# nine_poke_i2c.net
KiCad netlist of a schematic drawn in EAGLE
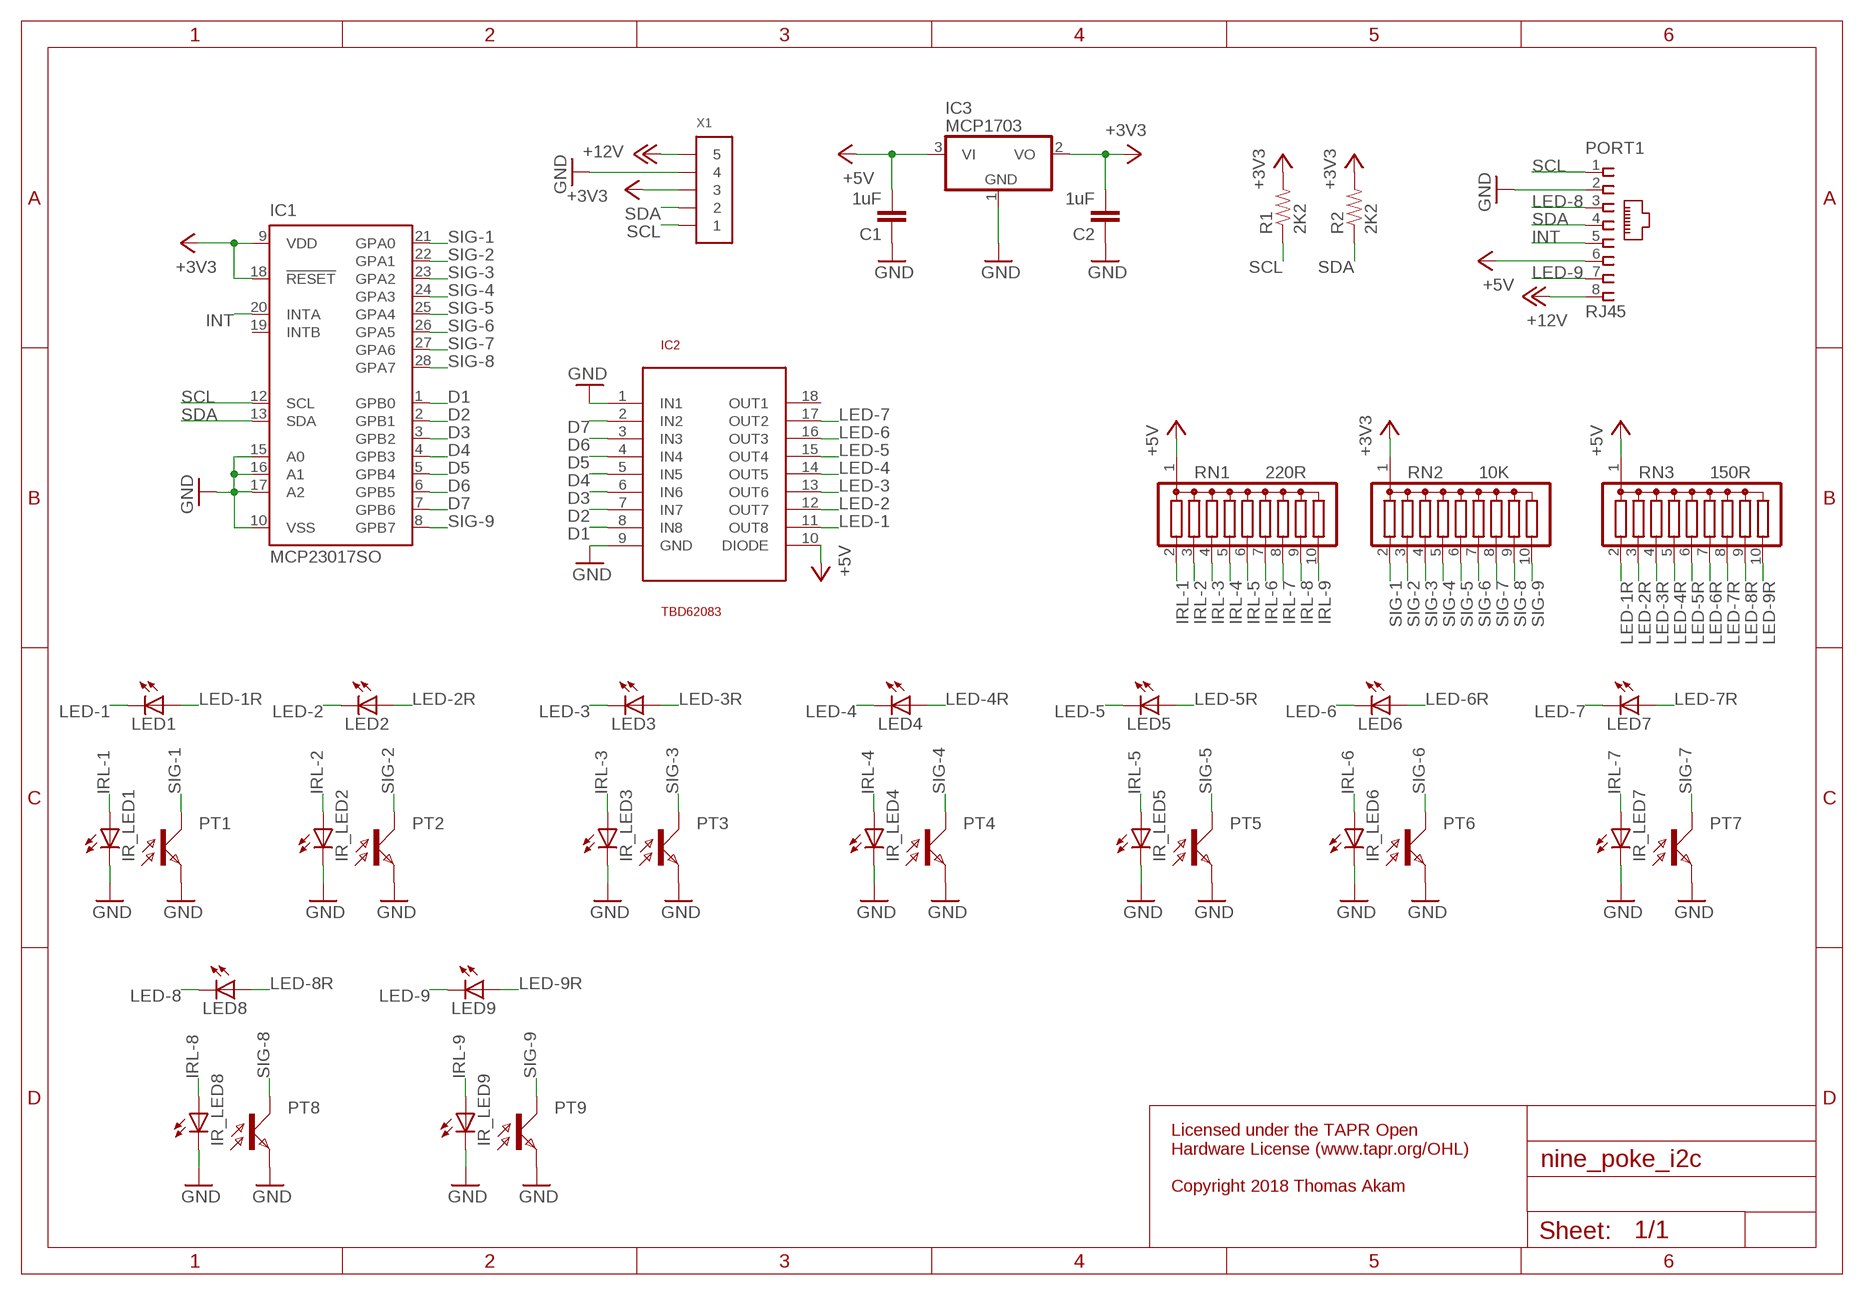
[diagram p0: schematic, sheet 1]

(export (version "E")
  (design (tool "Eeschema 10.0.6"))
  (components
    (comp (ref "C1")
      (value "1uF")
      (footprint "eagle-import:C0805")
      (libsource (lib "eagle-import") (part "C-EUC0805"))
    )
    (comp (ref "C2")
      (value "1uF")
      (footprint "eagle-import:C0805")
      (libsource (lib "eagle-import") (part "C-EUC0805"))
    )
    (comp (ref "IC1")
      (value "MCP23017SO")
      (footprint "eagle-import:SO28W")
      (fields (field (name "MF") "MICROCHIP") (field (name "MPN") "MCP23017-E/SO"))
      (libsource (lib "eagle-import") (part "MCP23017SO"))
    )
    (comp (ref "IC2")
      (value "TBD62083")
      (footprint "eagle-import:SO18L")
      (libsource (lib "eagle-import") (part "ULN2803"))
    )
    (comp (ref "IC3")
      (value "MCP1703")
      (footprint "eagle-import:SOT23")
      (libsource (lib "eagle-import") (part "MCP1703CB"))
    )
    (comp (ref "IR_LED1")
      (value "LEDIRL80A")
      (footprint "eagle-import:IRL80A")
      (libsource (lib "eagle-import") (part "LEDIRL80A"))
    )
    (comp (ref "IR_LED2")
      (value "LEDIRL80A")
      (footprint "eagle-import:IRL80A")
      (libsource (lib "eagle-import") (part "LEDIRL80A"))
    )
    (comp (ref "IR_LED3")
      (value "LEDIRL80A")
      (footprint "eagle-import:IRL80A")
      (libsource (lib "eagle-import") (part "LEDIRL80A"))
    )
    (comp (ref "IR_LED4")
      (value "LEDIRL80A")
      (footprint "eagle-import:IRL80A")
      (libsource (lib "eagle-import") (part "LEDIRL80A"))
    )
    (comp (ref "IR_LED5")
      (value "LEDIRL80A")
      (footprint "eagle-import:IRL80A")
      (libsource (lib "eagle-import") (part "LEDIRL80A"))
    )
    (comp (ref "IR_LED6")
      (value "LEDIRL80A")
      (footprint "eagle-import:IRL80A")
      (libsource (lib "eagle-import") (part "LEDIRL80A"))
    )
    (comp (ref "IR_LED7")
      (value "LEDIRL80A")
      (footprint "eagle-import:IRL80A")
      (libsource (lib "eagle-import") (part "LEDIRL80A"))
    )
    (comp (ref "IR_LED8")
      (value "LEDIRL80A")
      (footprint "eagle-import:IRL80A")
      (libsource (lib "eagle-import") (part "LEDIRL80A"))
    )
    (comp (ref "IR_LED9")
      (value "LEDIRL80A")
      (footprint "eagle-import:IRL80A")
      (libsource (lib "eagle-import") (part "LEDIRL80A"))
    )
    (comp (ref "LED1")
      (value "LEDSML0805")
      (footprint "eagle-import:SML0805")
      (libsource (lib "eagle-import") (part "LEDSML0805"))
    )
    (comp (ref "LED2")
      (value "LEDSML0805")
      (footprint "eagle-import:SML0805")
      (libsource (lib "eagle-import") (part "LEDSML0805"))
    )
    (comp (ref "LED3")
      (value "LEDSML0805")
      (footprint "eagle-import:SML0805")
      (libsource (lib "eagle-import") (part "LEDSML0805"))
    )
    (comp (ref "LED4")
      (value "LEDSML0805")
      (footprint "eagle-import:SML0805")
      (libsource (lib "eagle-import") (part "LEDSML0805"))
    )
    (comp (ref "LED5")
      (value "LEDSML0805")
      (footprint "eagle-import:SML0805")
      (libsource (lib "eagle-import") (part "LEDSML0805"))
    )
    (comp (ref "LED6")
      (value "LEDSML0805")
      (footprint "eagle-import:SML0805")
      (libsource (lib "eagle-import") (part "LEDSML0805"))
    )
    (comp (ref "LED7")
      (value "LEDSML0805")
      (footprint "eagle-import:SML0805")
      (libsource (lib "eagle-import") (part "LEDSML0805"))
    )
    (comp (ref "LED8")
      (value "LEDSML0805")
      (footprint "eagle-import:SML0805")
      (libsource (lib "eagle-import") (part "LEDSML0805"))
    )
    (comp (ref "LED9")
      (value "LEDSML0805")
      (footprint "eagle-import:SML0805")
      (libsource (lib "eagle-import") (part "LEDSML0805"))
    )
    (comp (ref "PORT1")
      (value "RJ45")
      (footprint "eagle-import:RJ45-NO-SHIELD-VERTICAL")
      (libsource (lib "eagle-import") (part "RJ45VERTICAL"))
    )
    (comp (ref "PT1")
      (value "LPT80A")
      (footprint "eagle-import:LPT80A")
      (fields (field (name "OC_FARNELL") "unknown") (field (name "OC_NEWARK") "unknown"))
      (libsource (lib "eagle-import") (part "LPT80A"))
    )
    (comp (ref "PT2")
      (value "LPT80A")
      (footprint "eagle-import:LPT80A")
      (fields (field (name "OC_FARNELL") "unknown") (field (name "OC_NEWARK") "unknown"))
      (libsource (lib "eagle-import") (part "LPT80A"))
    )
    (comp (ref "PT3")
      (value "LPT80A")
      (footprint "eagle-import:LPT80A")
      (fields (field (name "OC_FARNELL") "unknown") (field (name "OC_NEWARK") "unknown"))
      (libsource (lib "eagle-import") (part "LPT80A"))
    )
    (comp (ref "PT4")
      (value "LPT80A")
      (footprint "eagle-import:LPT80A")
      (fields (field (name "OC_FARNELL") "unknown") (field (name "OC_NEWARK") "unknown"))
      (libsource (lib "eagle-import") (part "LPT80A"))
    )
    (comp (ref "PT5")
      (value "LPT80A")
      (footprint "eagle-import:LPT80A")
      (fields (field (name "OC_FARNELL") "unknown") (field (name "OC_NEWARK") "unknown"))
      (libsource (lib "eagle-import") (part "LPT80A"))
    )
    (comp (ref "PT6")
      (value "LPT80A")
      (footprint "eagle-import:LPT80A")
      (fields (field (name "OC_FARNELL") "unknown") (field (name "OC_NEWARK") "unknown"))
      (libsource (lib "eagle-import") (part "LPT80A"))
    )
    (comp (ref "PT7")
      (value "LPT80A")
      (footprint "eagle-import:LPT80A")
      (fields (field (name "OC_FARNELL") "unknown") (field (name "OC_NEWARK") "unknown"))
      (libsource (lib "eagle-import") (part "LPT80A"))
    )
    (comp (ref "PT8")
      (value "LPT80A")
      (footprint "eagle-import:LPT80A")
      (fields (field (name "OC_FARNELL") "unknown") (field (name "OC_NEWARK") "unknown"))
      (libsource (lib "eagle-import") (part "LPT80A"))
    )
    (comp (ref "PT9")
      (value "LPT80A")
      (footprint "eagle-import:LPT80A")
      (fields (field (name "OC_FARNELL") "unknown") (field (name "OC_NEWARK") "unknown"))
      (libsource (lib "eagle-import") (part "LPT80A"))
    )
    (comp (ref "R1")
      (value "2K2")
      (footprint "eagle-import:0805")
      (libsource (lib "eagle-import") (part "0.3OHM-1/8W-1%(0805)"))
    )
    (comp (ref "R2")
      (value "2K2")
      (footprint "eagle-import:0805")
      (libsource (lib "eagle-import") (part "0.3OHM-1/8W-1%(0805)"))
    )
    (comp (ref "RN1")
      (value "220R")
      (footprint "eagle-import:SIL10")
      (libsource (lib "eagle-import") (part "G09R"))
    )
    (comp (ref "RN2")
      (value "10K")
      (footprint "eagle-import:SIL10")
      (libsource (lib "eagle-import") (part "G09R"))
    )
    (comp (ref "RN3")
      (value "150R")
      (footprint "eagle-import:SIL10")
      (libsource (lib "eagle-import") (part "G09R"))
    )
    (comp (ref "X1")
      (value "CONN_5-1-53398")
      (footprint "eagle-import:PB-53398-05")
      (libsource (lib "eagle-import") (part "CONN_5-1-53398"))
    )
  )
  (nets
    (net (code "1") (name "+3V3") (class "Default")
      (node (ref "C2") (pin "2") (pinfunction "2_2") (pintype "passive"))
      (node (ref "IC1") (pin "18") (pinfunction "~{RESET}_18") (pintype "input"))
      (node (ref "IC1") (pin "9") (pinfunction "VDD_9") (pintype "power_in"))
      (node (ref "IC3") (pin "2") (pinfunction "VO_2") (pintype "passive"))
      (node (ref "R1") (pin "2") (pinfunction "2_2") (pintype "passive"))
      (node (ref "R2") (pin "2") (pinfunction "2_2") (pintype "passive"))
      (node (ref "RN2") (pin "1") (pinfunction "1_1") (pintype "passive"))
      (node (ref "X1") (pin "3") (pinfunction "3_3") (pintype "bidirectional"))
    )
    (net (code "2") (name "+5V") (class "Default")
      (node (ref "C1") (pin "2") (pinfunction "2_2") (pintype "passive"))
      (node (ref "IC2") (pin "10") (pinfunction "DIODE_10") (pintype "power_in"))
      (node (ref "IC3") (pin "3") (pinfunction "VI_3") (pintype "input"))
      (node (ref "PORT1") (pin "6") (pinfunction "6_6") (pintype "passive"))
      (node (ref "RN1") (pin "1") (pinfunction "1_1") (pintype "passive"))
      (node (ref "RN3") (pin "1") (pinfunction "1_1") (pintype "passive"))
    )
    (net (code "3") (name "+12V") (class "Default")
      (node (ref "PORT1") (pin "8") (pinfunction "8_8") (pintype "passive"))
      (node (ref "X1") (pin "5") (pinfunction "5_5") (pintype "bidirectional"))
    )
    (net (code "4") (name "/D1") (class "Default")
      (node (ref "IC1") (pin "1") (pinfunction "GPB0_1") (pintype "bidirectional"))
      (node (ref "IC2") (pin "8") (pinfunction "IN8_8") (pintype "input"))
    )
    (net (code "5") (name "/D2") (class "Default")
      (node (ref "IC1") (pin "2") (pinfunction "GPB1_2") (pintype "bidirectional"))
      (node (ref "IC2") (pin "7") (pinfunction "IN7_7") (pintype "input"))
    )
    (net (code "6") (name "/D3") (class "Default")
      (node (ref "IC1") (pin "3") (pinfunction "GPB2_3") (pintype "bidirectional"))
      (node (ref "IC2") (pin "6") (pinfunction "IN6_6") (pintype "input"))
    )
    (net (code "7") (name "/D4") (class "Default")
      (node (ref "IC1") (pin "4") (pinfunction "GPB3_4") (pintype "bidirectional"))
      (node (ref "IC2") (pin "5") (pinfunction "IN5_5") (pintype "input"))
    )
    (net (code "8") (name "/D5") (class "Default")
      (node (ref "IC1") (pin "5") (pinfunction "GPB4_5") (pintype "bidirectional"))
      (node (ref "IC2") (pin "4") (pinfunction "IN4_4") (pintype "input"))
    )
    (net (code "9") (name "/D6") (class "Default")
      (node (ref "IC1") (pin "6") (pinfunction "GPB5_6") (pintype "bidirectional"))
      (node (ref "IC2") (pin "3") (pinfunction "IN3_3") (pintype "input"))
    )
    (net (code "10") (name "/D7") (class "Default")
      (node (ref "IC1") (pin "7") (pinfunction "GPB6_7") (pintype "bidirectional"))
      (node (ref "IC2") (pin "2") (pinfunction "IN2_2") (pintype "input"))
    )
    (net (code "11") (name "/INT") (class "Default")
      (node (ref "IC1") (pin "20") (pinfunction "INTA_20") (pintype "output"))
      (node (ref "PORT1") (pin "5") (pinfunction "5_5") (pintype "passive"))
    )
    (net (code "12") (name "/IRL-1") (class "Default")
      (node (ref "IR_LED1") (pin "A") (pinfunction "A_A") (pintype "passive"))
      (node (ref "RN1") (pin "2") (pinfunction "2_2") (pintype "passive"))
    )
    (net (code "13") (name "/IRL-2") (class "Default")
      (node (ref "IR_LED2") (pin "A") (pinfunction "A_A") (pintype "passive"))
      (node (ref "RN1") (pin "3") (pinfunction "3_3") (pintype "passive"))
    )
    (net (code "14") (name "/IRL-3") (class "Default")
      (node (ref "IR_LED3") (pin "A") (pinfunction "A_A") (pintype "passive"))
      (node (ref "RN1") (pin "4") (pinfunction "4_4") (pintype "passive"))
    )
    (net (code "15") (name "/IRL-4") (class "Default")
      (node (ref "IR_LED4") (pin "A") (pinfunction "A_A") (pintype "passive"))
      (node (ref "RN1") (pin "5") (pinfunction "5_5") (pintype "passive"))
    )
    (net (code "16") (name "/IRL-5") (class "Default")
      (node (ref "IR_LED5") (pin "A") (pinfunction "A_A") (pintype "passive"))
      (node (ref "RN1") (pin "6") (pinfunction "6_6") (pintype "passive"))
    )
    (net (code "17") (name "/IRL-6") (class "Default")
      (node (ref "IR_LED6") (pin "A") (pinfunction "A_A") (pintype "passive"))
      (node (ref "RN1") (pin "7") (pinfunction "7_7") (pintype "passive"))
    )
    (net (code "18") (name "/IRL-7") (class "Default")
      (node (ref "IR_LED7") (pin "A") (pinfunction "A_A") (pintype "passive"))
      (node (ref "RN1") (pin "8") (pinfunction "8_8") (pintype "passive"))
    )
    (net (code "19") (name "/IRL-8") (class "Default")
      (node (ref "IR_LED8") (pin "A") (pinfunction "A_A") (pintype "passive"))
      (node (ref "RN1") (pin "9") (pinfunction "9_9") (pintype "passive"))
    )
    (net (code "20") (name "/IRL-9") (class "Default")
      (node (ref "IR_LED9") (pin "A") (pinfunction "A_A") (pintype "passive"))
      (node (ref "RN1") (pin "10") (pinfunction "10_10") (pintype "passive"))
    )
    (net (code "21") (name "/LED-1") (class "Default")
      (node (ref "IC2") (pin "11") (pinfunction "OUT8_11") (pintype "open_collector"))
      (node (ref "LED1") (pin "C") (pinfunction "C_C") (pintype "passive"))
    )
    (net (code "22") (name "/LED-1R") (class "Default")
      (node (ref "LED1") (pin "A") (pinfunction "A_A") (pintype "passive"))
      (node (ref "RN3") (pin "2") (pinfunction "2_2") (pintype "passive"))
    )
    (net (code "23") (name "/LED-2") (class "Default")
      (node (ref "IC2") (pin "12") (pinfunction "OUT7_12") (pintype "open_collector"))
      (node (ref "LED2") (pin "C") (pinfunction "C_C") (pintype "passive"))
    )
    (net (code "24") (name "/LED-2R") (class "Default")
      (node (ref "LED2") (pin "A") (pinfunction "A_A") (pintype "passive"))
      (node (ref "RN3") (pin "3") (pinfunction "3_3") (pintype "passive"))
    )
    (net (code "25") (name "/LED-3") (class "Default")
      (node (ref "IC2") (pin "13") (pinfunction "OUT6_13") (pintype "open_collector"))
      (node (ref "LED3") (pin "C") (pinfunction "C_C") (pintype "passive"))
    )
    (net (code "26") (name "/LED-3R") (class "Default")
      (node (ref "LED3") (pin "A") (pinfunction "A_A") (pintype "passive"))
      (node (ref "RN3") (pin "4") (pinfunction "4_4") (pintype "passive"))
    )
    (net (code "27") (name "/LED-4") (class "Default")
      (node (ref "IC2") (pin "14") (pinfunction "OUT5_14") (pintype "open_collector"))
      (node (ref "LED4") (pin "C") (pinfunction "C_C") (pintype "passive"))
    )
    (net (code "28") (name "/LED-4R") (class "Default")
      (node (ref "LED4") (pin "A") (pinfunction "A_A") (pintype "passive"))
      (node (ref "RN3") (pin "5") (pinfunction "5_5") (pintype "passive"))
    )
    (net (code "29") (name "/LED-5") (class "Default")
      (node (ref "IC2") (pin "15") (pinfunction "OUT4_15") (pintype "open_collector"))
      (node (ref "LED5") (pin "C") (pinfunction "C_C") (pintype "passive"))
    )
    (net (code "30") (name "/LED-5R") (class "Default")
      (node (ref "LED5") (pin "A") (pinfunction "A_A") (pintype "passive"))
      (node (ref "RN3") (pin "6") (pinfunction "6_6") (pintype "passive"))
    )
    (net (code "31") (name "/LED-6") (class "Default")
      (node (ref "IC2") (pin "16") (pinfunction "OUT3_16") (pintype "open_collector"))
      (node (ref "LED6") (pin "C") (pinfunction "C_C") (pintype "passive"))
    )
    (net (code "32") (name "/LED-6R") (class "Default")
      (node (ref "LED6") (pin "A") (pinfunction "A_A") (pintype "passive"))
      (node (ref "RN3") (pin "7") (pinfunction "7_7") (pintype "passive"))
    )
    (net (code "33") (name "/LED-7") (class "Default")
      (node (ref "IC2") (pin "17") (pinfunction "OUT2_17") (pintype "open_collector"))
      (node (ref "LED7") (pin "C") (pinfunction "C_C") (pintype "passive"))
    )
    (net (code "34") (name "/LED-7R") (class "Default")
      (node (ref "LED7") (pin "A") (pinfunction "A_A") (pintype "passive"))
      (node (ref "RN3") (pin "8") (pinfunction "8_8") (pintype "passive"))
    )
    (net (code "35") (name "/LED-8") (class "Default")
      (node (ref "LED8") (pin "C") (pinfunction "C_C") (pintype "passive"))
      (node (ref "PORT1") (pin "3") (pinfunction "3_3") (pintype "passive"))
    )
    (net (code "36") (name "/LED-8R") (class "Default")
      (node (ref "LED8") (pin "A") (pinfunction "A_A") (pintype "passive"))
      (node (ref "RN3") (pin "9") (pinfunction "9_9") (pintype "passive"))
    )
    (net (code "37") (name "/LED-9") (class "Default")
      (node (ref "LED9") (pin "C") (pinfunction "C_C") (pintype "passive"))
      (node (ref "PORT1") (pin "7") (pinfunction "7_7") (pintype "passive"))
    )
    (net (code "38") (name "/LED-9R") (class "Default")
      (node (ref "LED9") (pin "A") (pinfunction "A_A") (pintype "passive"))
      (node (ref "RN3") (pin "10") (pinfunction "10_10") (pintype "passive"))
    )
    (net (code "39") (name "/SCL") (class "Default")
      (node (ref "IC1") (pin "12") (pinfunction "SCL_12") (pintype "input"))
      (node (ref "PORT1") (pin "1") (pinfunction "1_1") (pintype "passive"))
      (node (ref "R1") (pin "1") (pinfunction "1_1") (pintype "passive"))
      (node (ref "X1") (pin "1") (pinfunction "1_1") (pintype "bidirectional"))
    )
    (net (code "40") (name "/SDA") (class "Default")
      (node (ref "IC1") (pin "13") (pinfunction "SDA_13") (pintype "bidirectional"))
      (node (ref "PORT1") (pin "4") (pinfunction "4_4") (pintype "passive"))
      (node (ref "R2") (pin "1") (pinfunction "1_1") (pintype "passive"))
      (node (ref "X1") (pin "2") (pinfunction "2_2") (pintype "bidirectional"))
    )
    (net (code "41") (name "/SIG-1") (class "Default")
      (node (ref "IC1") (pin "21") (pinfunction "GPA0_21") (pintype "bidirectional"))
      (node (ref "PT1") (pin "C") (pinfunction "C_C") (pintype "passive"))
      (node (ref "RN2") (pin "2") (pinfunction "2_2") (pintype "passive"))
    )
    (net (code "42") (name "/SIG-2") (class "Default")
      (node (ref "IC1") (pin "22") (pinfunction "GPA1_22") (pintype "bidirectional"))
      (node (ref "PT2") (pin "C") (pinfunction "C_C") (pintype "passive"))
      (node (ref "RN2") (pin "3") (pinfunction "3_3") (pintype "passive"))
    )
    (net (code "43") (name "/SIG-3") (class "Default")
      (node (ref "IC1") (pin "23") (pinfunction "GPA2_23") (pintype "bidirectional"))
      (node (ref "PT3") (pin "C") (pinfunction "C_C") (pintype "passive"))
      (node (ref "RN2") (pin "4") (pinfunction "4_4") (pintype "passive"))
    )
    (net (code "44") (name "/SIG-4") (class "Default")
      (node (ref "IC1") (pin "24") (pinfunction "GPA3_24") (pintype "bidirectional"))
      (node (ref "PT4") (pin "C") (pinfunction "C_C") (pintype "passive"))
      (node (ref "RN2") (pin "5") (pinfunction "5_5") (pintype "passive"))
    )
    (net (code "45") (name "/SIG-5") (class "Default")
      (node (ref "IC1") (pin "25") (pinfunction "GPA4_25") (pintype "bidirectional"))
      (node (ref "PT5") (pin "C") (pinfunction "C_C") (pintype "passive"))
      (node (ref "RN2") (pin "6") (pinfunction "6_6") (pintype "passive"))
    )
    (net (code "46") (name "/SIG-6") (class "Default")
      (node (ref "IC1") (pin "26") (pinfunction "GPA5_26") (pintype "bidirectional"))
      (node (ref "PT6") (pin "C") (pinfunction "C_C") (pintype "passive"))
      (node (ref "RN2") (pin "7") (pinfunction "7_7") (pintype "passive"))
    )
    (net (code "47") (name "/SIG-7") (class "Default")
      (node (ref "IC1") (pin "27") (pinfunction "GPA6_27") (pintype "bidirectional"))
      (node (ref "PT7") (pin "C") (pinfunction "C_C") (pintype "passive"))
      (node (ref "RN2") (pin "8") (pinfunction "8_8") (pintype "passive"))
    )
    (net (code "48") (name "/SIG-8") (class "Default")
      (node (ref "IC1") (pin "28") (pinfunction "GPA7_28") (pintype "bidirectional"))
      (node (ref "PT8") (pin "C") (pinfunction "C_C") (pintype "passive"))
      (node (ref "RN2") (pin "9") (pinfunction "9_9") (pintype "passive"))
    )
    (net (code "49") (name "/SIG-9") (class "Default")
      (node (ref "IC1") (pin "8") (pinfunction "GPB7_8") (pintype "bidirectional"))
      (node (ref "PT9") (pin "C") (pinfunction "C_C") (pintype "passive"))
      (node (ref "RN2") (pin "10") (pinfunction "10_10") (pintype "passive"))
    )
    (net (code "50") (name "GND") (class "Default")
      (node (ref "C1") (pin "1") (pinfunction "1_1") (pintype "passive"))
      (node (ref "C2") (pin "1") (pinfunction "1_1") (pintype "passive"))
      (node (ref "IC1") (pin "10") (pinfunction "VSS_10") (pintype "power_in"))
      (node (ref "IC1") (pin "15") (pinfunction "A0_15") (pintype "input"))
      (node (ref "IC1") (pin "16") (pinfunction "A1_16") (pintype "input"))
      (node (ref "IC1") (pin "17") (pinfunction "A2_17") (pintype "input"))
      (node (ref "IC2") (pin "1") (pinfunction "IN1_1") (pintype "input"))
      (node (ref "IC2") (pin "9") (pinfunction "GND_9") (pintype "power_in"))
      (node (ref "IC3") (pin "1") (pinfunction "GND_1") (pintype "passive"))
      (node (ref "IR_LED1") (pin "K") (pinfunction "C_K") (pintype "passive"))
      (node (ref "IR_LED2") (pin "K") (pinfunction "C_K") (pintype "passive"))
      (node (ref "IR_LED3") (pin "K") (pinfunction "C_K") (pintype "passive"))
      (node (ref "IR_LED4") (pin "K") (pinfunction "C_K") (pintype "passive"))
      (node (ref "IR_LED5") (pin "K") (pinfunction "C_K") (pintype "passive"))
      (node (ref "IR_LED6") (pin "K") (pinfunction "C_K") (pintype "passive"))
      (node (ref "IR_LED7") (pin "K") (pinfunction "C_K") (pintype "passive"))
      (node (ref "IR_LED8") (pin "K") (pinfunction "C_K") (pintype "passive"))
      (node (ref "IR_LED9") (pin "K") (pinfunction "C_K") (pintype "passive"))
      (node (ref "PORT1") (pin "2") (pinfunction "2_2") (pintype "passive"))
      (node (ref "PT1") (pin "E") (pinfunction "E_E") (pintype "passive"))
      (node (ref "PT2") (pin "E") (pinfunction "E_E") (pintype "passive"))
      (node (ref "PT3") (pin "E") (pinfunction "E_E") (pintype "passive"))
      (node (ref "PT4") (pin "E") (pinfunction "E_E") (pintype "passive"))
      (node (ref "PT5") (pin "E") (pinfunction "E_E") (pintype "passive"))
      (node (ref "PT6") (pin "E") (pinfunction "E_E") (pintype "passive"))
      (node (ref "PT7") (pin "E") (pinfunction "E_E") (pintype "passive"))
      (node (ref "PT8") (pin "E") (pinfunction "E_E") (pintype "passive"))
      (node (ref "PT9") (pin "E") (pinfunction "E_E") (pintype "passive"))
      (node (ref "X1") (pin "4") (pinfunction "4_4") (pintype "bidirectional"))
    )
    (net (code "51") (name "unconnected-(IC1-INTB-Pad19)") (class "Default")
      (node (ref "IC1") (pin "19") (pinfunction "INTB_19") (pintype "output"))
    )
    (net (code "52") (name "unconnected-(IC2-OUT1-Pad18)") (class "Default")
      (node (ref "IC2") (pin "18") (pinfunction "OUT1_18") (pintype "open_collector"))
    )
  )
)
